# USB2Serial_CH340G_v1_1.net
KiCad netlist of a schematic drawn in EAGLE
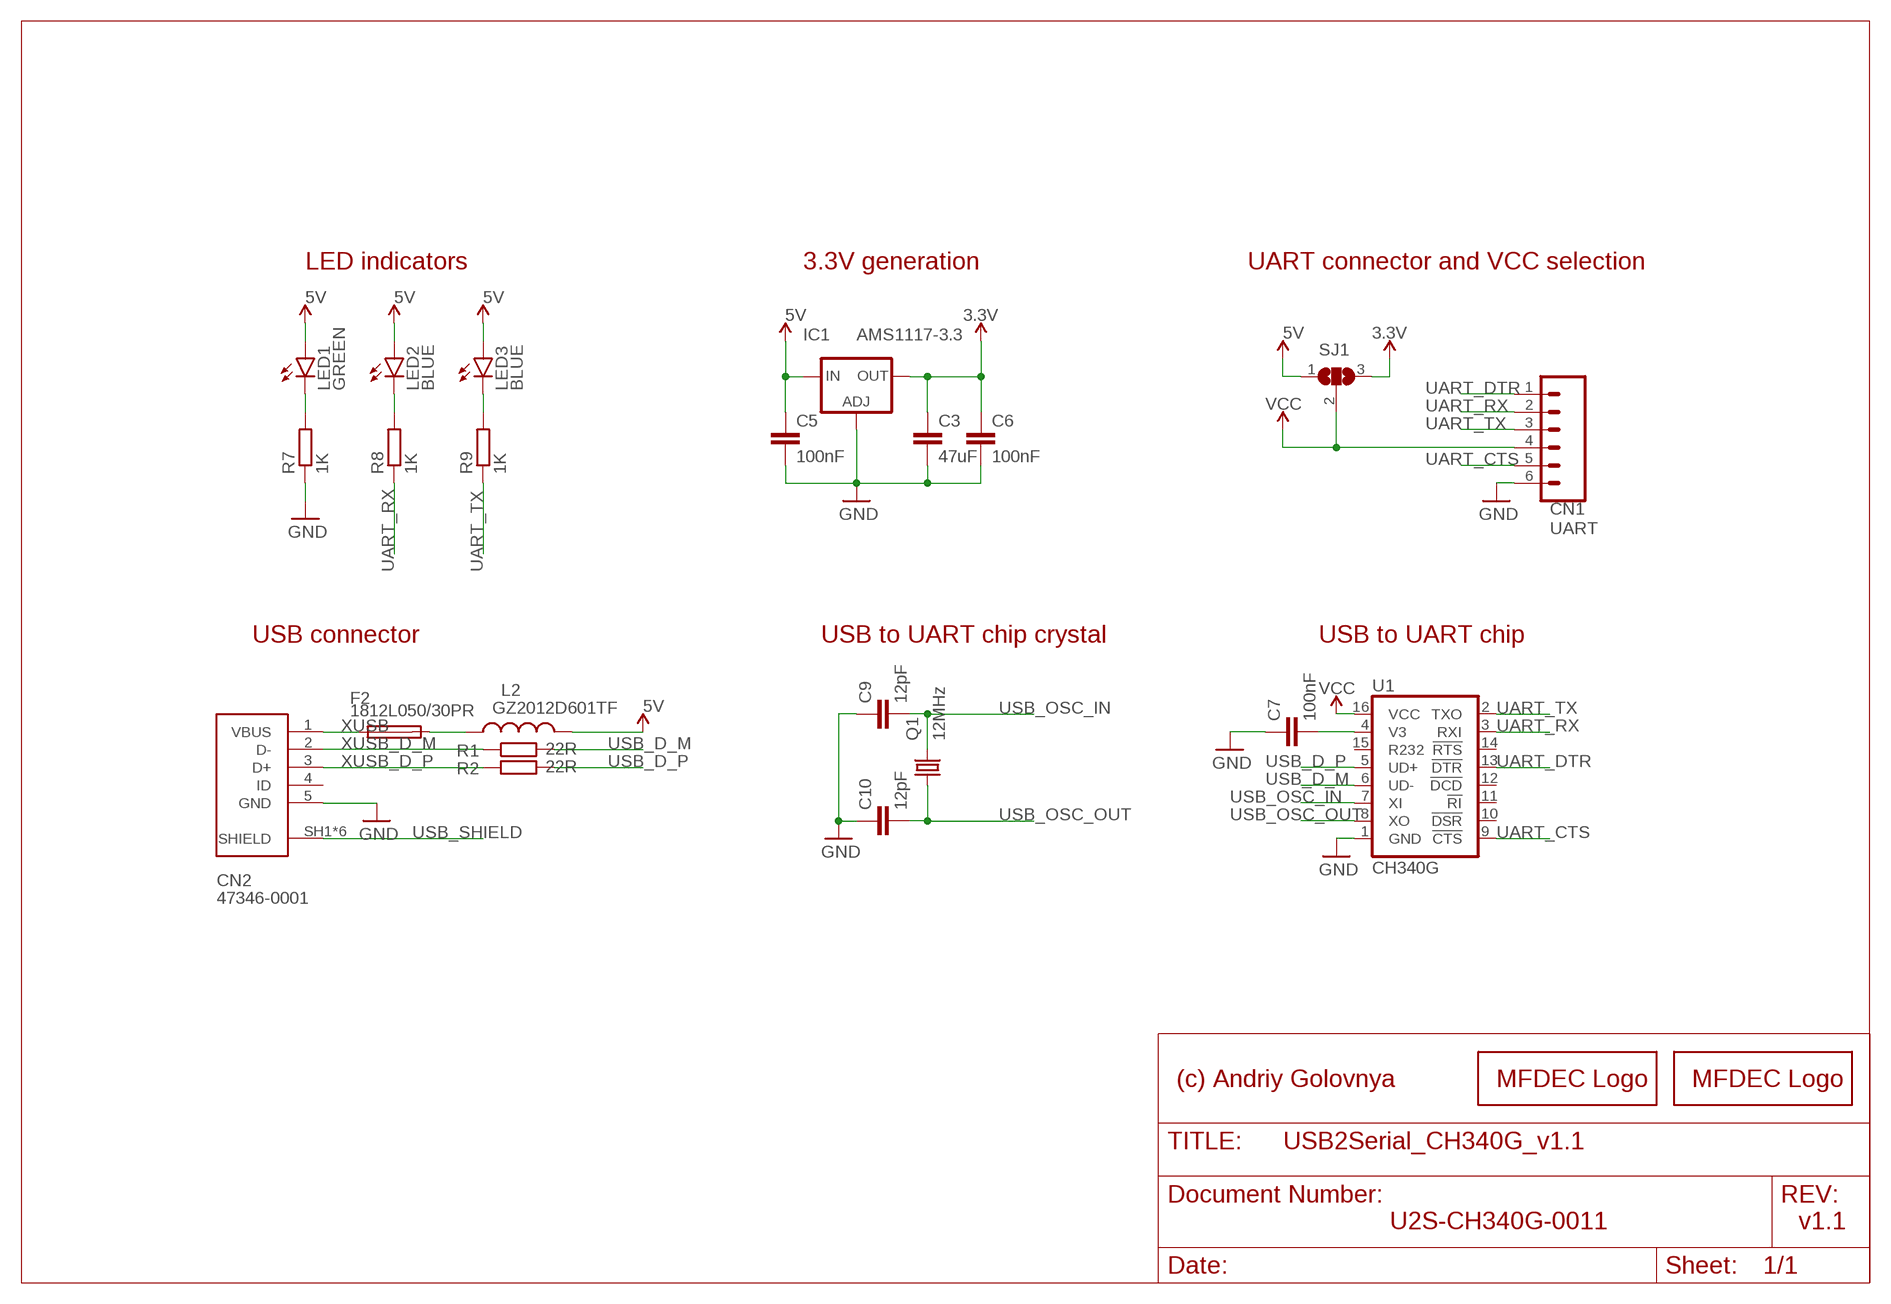
[diagram p0: schematic, sheet 1]

(export (version "E")
  (design (tool "Eeschema 10.0.6"))
  (components
    (comp (ref "C3")
      (value "47uF")
      (footprint "eagle-import:C0805")
      (libsource (lib "eagle-import") (part "C-EUC0805"))
    )
    (comp (ref "C5")
      (value "100nF")
      (footprint "eagle-import:C0402")
      (libsource (lib "eagle-import") (part "C-EUC0402"))
    )
    (comp (ref "C6")
      (value "100nF")
      (footprint "eagle-import:C0402")
      (libsource (lib "eagle-import") (part "C-EUC0402"))
    )
    (comp (ref "C7")
      (value "100nF")
      (footprint "eagle-import:C0402")
      (libsource (lib "eagle-import") (part "C-EUC0402"))
    )
    (comp (ref "C9")
      (value "12pF")
      (footprint "eagle-import:C0402")
      (libsource (lib "eagle-import") (part "C-EUC0402"))
    )
    (comp (ref "C10")
      (value "12pF")
      (footprint "eagle-import:C0402")
      (libsource (lib "eagle-import") (part "C-EUC0402"))
    )
    (comp (ref "CN1")
      (value "UART")
      (footprint "eagle-import:1X06_LOCK")
      (libsource (lib "eagle-import") (part "CONN_06LOCK"))
    )
    (comp (ref "CN2")
      (value "47346-0001")
      (footprint "eagle-import:MOLEX_47346-0001")
      (fields (field (name "MANUFACTURER") "Molex"))
      (libsource (lib "eagle-import") (part "47346-0001"))
    )
    (comp (ref "F2")
      (value "1812L050/30PR")
      (footprint "eagle-import:MF-SMDF050")
      (libsource (lib "eagle-import") (part "MF-SMDF050"))
    )
    (comp (ref "IC1")
      (value "AMS1117-3.3")
      (footprint "eagle-import:SOT223")
      (libsource (lib "eagle-import") (part "LD117A?S33TR"))
    )
    (comp (ref "L2")
      (value "GZ2012D601TF")
      (footprint "eagle-import:WE-CBA_0805(W=4)")
      (libsource (lib "eagle-import") (part "WE-CBA_0805_HC_782853102"))
    )
    (comp (ref "LED1")
      (value "GREEN")
      (footprint "eagle-import:SML0603")
      (libsource (lib "eagle-import") (part "LEDSML0603"))
    )
    (comp (ref "LED2")
      (value "BLUE")
      (footprint "eagle-import:SML0603")
      (libsource (lib "eagle-import") (part "LEDSML0603"))
    )
    (comp (ref "LED3")
      (value "BLUE")
      (footprint "eagle-import:SML0603")
      (libsource (lib "eagle-import") (part "LEDSML0603"))
    )
    (comp (ref "LOGO1")
      (value "MFDECLOGO_L_20MM")
      (footprint "eagle-import:MFDEC_L_20MM")
      (libsource (lib "eagle-import") (part "MFDECLOGO_L_20MM"))
    )
    (comp (ref "LOGO2")
      (value "MFDECLOGO_SQ_10MM")
      (footprint "eagle-import:MFDEC_SQ_10MM")
      (libsource (lib "eagle-import") (part "MFDECLOGO_SQ_10MM"))
    )
    (comp (ref "Q1")
      (value "12MHz")
      (footprint "eagle-import:3.2X2.5_KX-7")
      (libsource (lib "eagle-import") (part "KX-7"))
    )
    (comp (ref "R1")
      (value "22R")
      (footprint "eagle-import:R0402")
      (libsource (lib "eagle-import") (part "R-EU_R0402"))
    )
    (comp (ref "R2")
      (value "22R")
      (footprint "eagle-import:R0402")
      (libsource (lib "eagle-import") (part "R-EU_R0402"))
    )
    (comp (ref "R7")
      (value "1K")
      (footprint "eagle-import:R0402")
      (libsource (lib "eagle-import") (part "R-EU_R0402"))
    )
    (comp (ref "R8")
      (value "1K")
      (footprint "eagle-import:R0402")
      (libsource (lib "eagle-import") (part "R-EU_R0402"))
    )
    (comp (ref "R9")
      (value "1K")
      (footprint "eagle-import:R0402")
      (libsource (lib "eagle-import") (part "R-EU_R0402"))
    )
    (comp (ref "SJ1")
      (value "SJ2FI")
      (footprint "eagle-import:SJ_2FI")
      (libsource (lib "eagle-import") (part "SJ2FI"))
    )
    (comp (ref "U1")
      (value "CH340G")
      (footprint "eagle-import:SO016")
      (libsource (lib "eagle-import") (part "CH340GSMD"))
    )
  )
  (nets
    (net (code "1") (name "/UART_CTS") (class "Default")
      (node (ref "CN1") (pin "5") (pinfunction "5_5") (pintype "passive"))
      (node (ref "U1") (pin "9") (pinfunction "~{CTS}_9") (pintype "bidirectional"))
    )
    (net (code "2") (name "/UART_DTR") (class "Default")
      (node (ref "CN1") (pin "1") (pinfunction "1_1") (pintype "passive"))
      (node (ref "U1") (pin "13") (pinfunction "~{DTR}_13") (pintype "bidirectional"))
    )
    (net (code "3") (name "/UART_RX") (class "Default")
      (node (ref "CN1") (pin "2") (pinfunction "2_2") (pintype "passive"))
      (node (ref "R8") (pin "1") (pinfunction "1_1") (pintype "passive"))
      (node (ref "U1") (pin "3") (pinfunction "RXI_3") (pintype "bidirectional"))
    )
    (net (code "4") (name "/UART_TX") (class "Default")
      (node (ref "CN1") (pin "3") (pinfunction "3_3") (pintype "passive"))
      (node (ref "R9") (pin "1") (pinfunction "1_1") (pintype "passive"))
      (node (ref "U1") (pin "2") (pinfunction "TXO_2") (pintype "bidirectional"))
    )
    (net (code "5") (name "/USB_D_M") (class "Default")
      (node (ref "R1") (pin "2") (pinfunction "2_2") (pintype "passive"))
      (node (ref "U1") (pin "6") (pinfunction "UD-_6") (pintype "bidirectional"))
    )
    (net (code "6") (name "/USB_D_P") (class "Default")
      (node (ref "R2") (pin "2") (pinfunction "2_2") (pintype "passive"))
      (node (ref "U1") (pin "5") (pinfunction "UD+_5") (pintype "bidirectional"))
    )
    (net (code "7") (name "/USB_OSC_IN") (class "Default")
      (node (ref "C9") (pin "2") (pinfunction "2_2") (pintype "passive"))
      (node (ref "Q1") (pin "3") (pinfunction "2_3") (pintype "passive"))
      (node (ref "U1") (pin "7") (pinfunction "XI_7") (pintype "bidirectional"))
    )
    (net (code "8") (name "/USB_OSC_OUT") (class "Default")
      (node (ref "C10") (pin "2") (pinfunction "2_2") (pintype "passive"))
      (node (ref "Q1") (pin "1") (pinfunction "1_1") (pintype "passive"))
      (node (ref "U1") (pin "8") (pinfunction "XO_8") (pintype "bidirectional"))
    )
    (net (code "9") (name "/USB_SHIELD") (class "Default")
      (node (ref "CN2") (pin "SH1") (pinfunction "SHIELD_SH1") (pintype "passive"))
      (node (ref "CN2") (pin "SH2") (pinfunction "SHIELD_SH2") (pintype "passive"))
      (node (ref "CN2") (pin "SH3") (pinfunction "SHIELD_SH3") (pintype "passive"))
      (node (ref "CN2") (pin "SH4") (pinfunction "SHIELD_SH4") (pintype "passive"))
      (node (ref "CN2") (pin "SH5") (pinfunction "SHIELD_SH5") (pintype "passive"))
      (node (ref "CN2") (pin "SH6") (pinfunction "SHIELD_SH6") (pintype "passive"))
    )
    (net (code "10") (name "/XUSB") (class "Default")
      (node (ref "CN2") (pin "1") (pinfunction "VBUS_1") (pintype "power_in"))
      (node (ref "F2") (pin "1") (pinfunction "1_1") (pintype "passive"))
    )
    (net (code "11") (name "/XUSB_D_M") (class "Default")
      (node (ref "CN2") (pin "2") (pinfunction "D-_2") (pintype "bidirectional"))
      (node (ref "R1") (pin "1") (pinfunction "1_1") (pintype "passive"))
    )
    (net (code "12") (name "/XUSB_D_P") (class "Default")
      (node (ref "CN2") (pin "3") (pinfunction "D+_3") (pintype "bidirectional"))
      (node (ref "R2") (pin "1") (pinfunction "1_1") (pintype "passive"))
    )
    (net (code "13") (name "3.3V") (class "Default")
      (node (ref "C3") (pin "1") (pinfunction "1_1") (pintype "passive"))
      (node (ref "C6") (pin "1") (pinfunction "1_1") (pintype "passive"))
      (node (ref "IC1") (pin "4") (pinfunction "OUT_4") (pintype "passive"))
      (node (ref "SJ1") (pin "3") (pinfunction "3_3") (pintype "passive"))
    )
    (net (code "14") (name "5V") (class "Default")
      (node (ref "C5") (pin "1") (pinfunction "1_1") (pintype "passive"))
      (node (ref "IC1") (pin "3") (pinfunction "IN_3") (pintype "input"))
      (node (ref "L2") (pin "2") (pinfunction "2_2") (pintype "passive"))
      (node (ref "LED1") (pin "A") (pinfunction "A_A") (pintype "passive"))
      (node (ref "LED2") (pin "A") (pinfunction "A_A") (pintype "passive"))
      (node (ref "LED3") (pin "A") (pinfunction "A_A") (pintype "passive"))
      (node (ref "SJ1") (pin "1") (pinfunction "1_1") (pintype "passive"))
    )
    (net (code "15") (name "GND") (class "Default")
      (node (ref "C10") (pin "1") (pinfunction "1_1") (pintype "passive"))
      (node (ref "C3") (pin "2") (pinfunction "2_2") (pintype "passive"))
      (node (ref "C5") (pin "2") (pinfunction "2_2") (pintype "passive"))
      (node (ref "C6") (pin "2") (pinfunction "2_2") (pintype "passive"))
      (node (ref "C7") (pin "1") (pinfunction "1_1") (pintype "passive"))
      (node (ref "C9") (pin "1") (pinfunction "1_1") (pintype "passive"))
      (node (ref "CN1") (pin "6") (pinfunction "6_6") (pintype "passive"))
      (node (ref "CN2") (pin "5") (pinfunction "GND_5") (pintype "power_in"))
      (node (ref "IC1") (pin "1") (pinfunction "ADJ_1") (pintype "input"))
      (node (ref "R7") (pin "1") (pinfunction "1_1") (pintype "passive"))
      (node (ref "U1") (pin "1") (pinfunction "GND_1") (pintype "bidirectional"))
    )
    (net (code "16") (name "Net-(F2-Pad2)") (class "Default")
      (node (ref "F2") (pin "2") (pinfunction "2_2") (pintype "passive"))
      (node (ref "L2") (pin "1") (pinfunction "1_1") (pintype "passive"))
    )
    (net (code "17") (name "Net-(LED1-PadC)") (class "Default")
      (node (ref "LED1") (pin "C") (pinfunction "C_C") (pintype "passive"))
      (node (ref "R7") (pin "2") (pinfunction "2_2") (pintype "passive"))
    )
    (net (code "18") (name "Net-(LED2-PadC)") (class "Default")
      (node (ref "LED2") (pin "C") (pinfunction "C_C") (pintype "passive"))
      (node (ref "R8") (pin "2") (pinfunction "2_2") (pintype "passive"))
    )
    (net (code "19") (name "Net-(LED3-PadC)") (class "Default")
      (node (ref "LED3") (pin "C") (pinfunction "C_C") (pintype "passive"))
      (node (ref "R9") (pin "2") (pinfunction "2_2") (pintype "passive"))
    )
    (net (code "20") (name "Net-(U1-V3)") (class "Default")
      (node (ref "C7") (pin "2") (pinfunction "2_2") (pintype "passive"))
      (node (ref "U1") (pin "4") (pinfunction "V3_4") (pintype "bidirectional"))
    )
    (net (code "21") (name "VCC") (class "Default")
      (node (ref "CN1") (pin "4") (pinfunction "4_4") (pintype "passive"))
      (node (ref "SJ1") (pin "2") (pinfunction "2_2") (pintype "passive"))
      (node (ref "U1") (pin "16") (pinfunction "VCC_16") (pintype "bidirectional"))
    )
    (net (code "22") (name "unconnected-(CN2-ID-Pad4)") (class "Default")
      (node (ref "CN2") (pin "4") (pinfunction "ID_4") (pintype "passive"))
    )
    (net (code "23") (name "unconnected-(U1-R232-Pad15)") (class "Default")
      (node (ref "U1") (pin "15") (pinfunction "R232_15") (pintype "bidirectional"))
    )
    (net (code "24") (name "unconnected-(U1-~{DCD}-Pad12)") (class "Default")
      (node (ref "U1") (pin "12") (pinfunction "~{DCD}_12") (pintype "bidirectional"))
    )
    (net (code "25") (name "unconnected-(U1-~{DSR}-Pad10)") (class "Default")
      (node (ref "U1") (pin "10") (pinfunction "~{DSR}_10") (pintype "bidirectional"))
    )
    (net (code "26") (name "unconnected-(U1-~{RI}-Pad11)") (class "Default")
      (node (ref "U1") (pin "11") (pinfunction "~{RI}_11") (pintype "bidirectional"))
    )
    (net (code "27") (name "unconnected-(U1-~{RTS}-Pad14)") (class "Default")
      (node (ref "U1") (pin "14") (pinfunction "~{RTS}_14") (pintype "bidirectional"))
    )
  )
)
